# Battery_old.net
KiCad netlist of a schematic drawn in Altium Designer
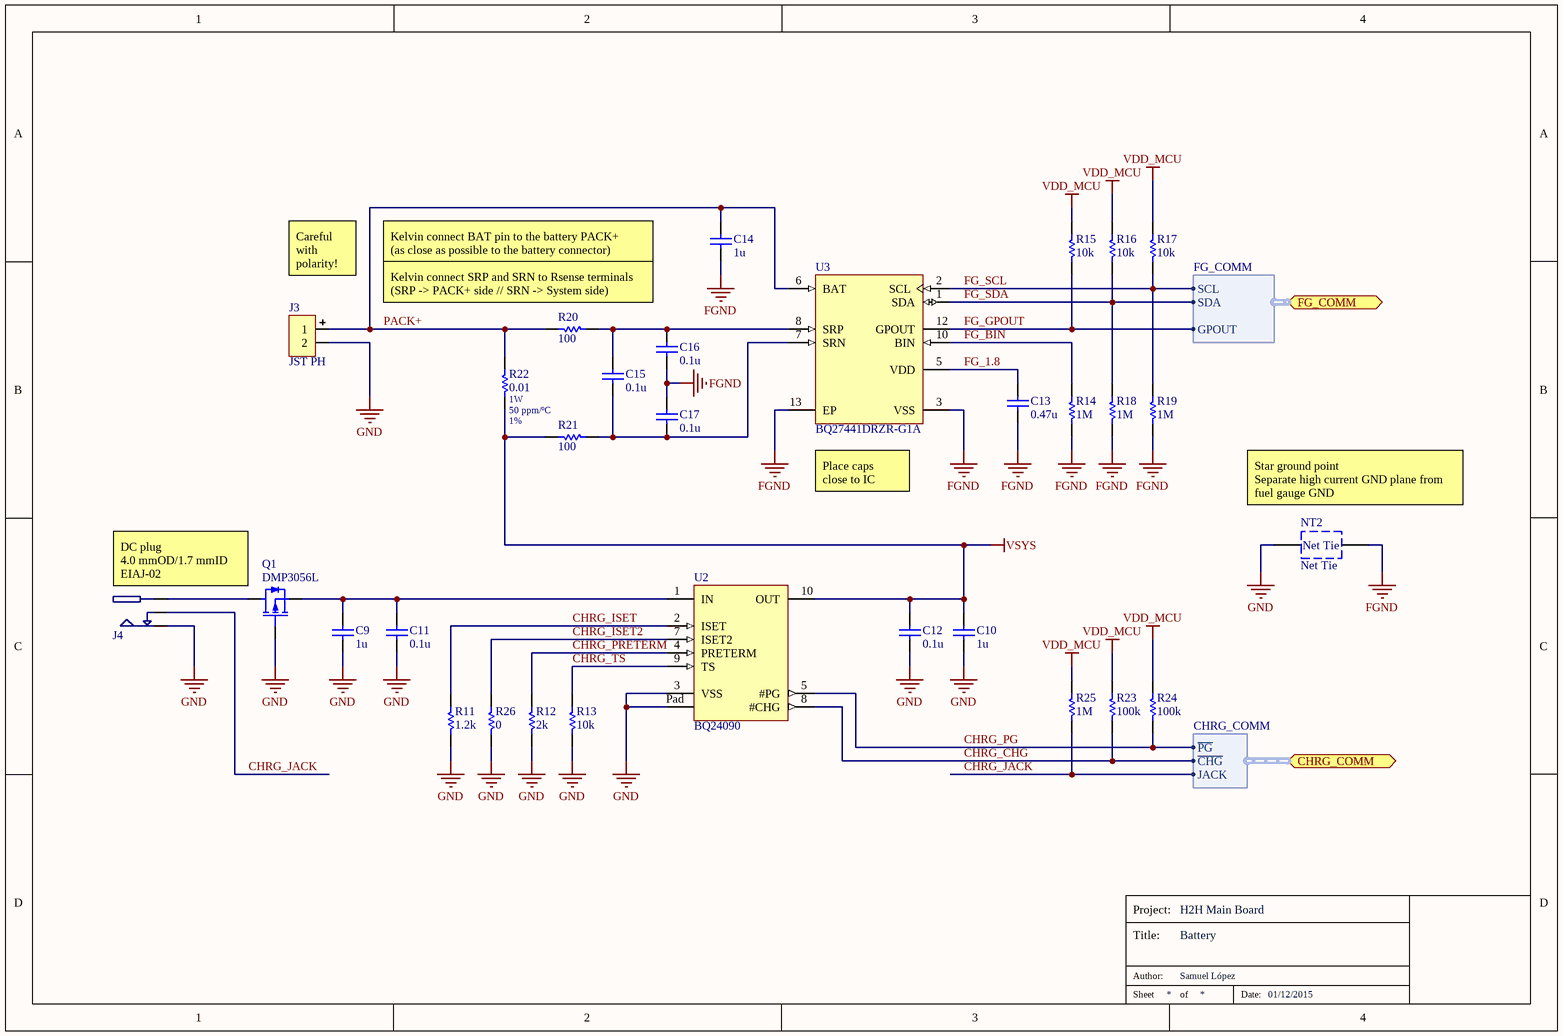
[diagram p0: Battery_old.SchDoc]

(export (version "E")
  (design (tool "Eeschema 10.0.6"))
  (components
    (comp (ref "C9")
      (value "1u")
      (footprint "C0603")
      (description "Capacitor")
      (libsource (lib "Common Devices") (part "Capacitor"))
    )
    (comp (ref "C10")
      (value "1u")
      (footprint "C0603")
      (description "Capacitor")
      (libsource (lib "Common Devices") (part "Capacitor"))
    )
    (comp (ref "C11")
      (value "0.1u")
      (footprint "C0603")
      (description "Capacitor")
      (libsource (lib "Common Devices") (part "Capacitor"))
    )
    (comp (ref "C12")
      (value "0.1u")
      (footprint "C0603")
      (description "Capacitor")
      (libsource (lib "Common Devices") (part "Capacitor"))
    )
    (comp (ref "C13")
      (value "0.47u")
      (footprint "C0603")
      (description "Capacitor")
      (libsource (lib "Common Devices") (part "Capacitor"))
    )
    (comp (ref "C14")
      (value "1u")
      (footprint "C0603")
      (description "Capacitor")
      (libsource (lib "Common Devices") (part "Capacitor"))
    )
    (comp (ref "C15")
      (value "0.1u")
      (footprint "C0603")
      (description "Capacitor")
      (libsource (lib "Common Devices") (part "Capacitor"))
    )
    (comp (ref "C16")
      (value "0.1u")
      (footprint "C0603")
      (description "Capacitor")
      (libsource (lib "Common Devices") (part "Capacitor"))
    )
    (comp (ref "C17")
      (value "0.1u")
      (footprint "C0603")
      (description "Capacitor")
      (libsource (lib "Common Devices") (part "Capacitor"))
    )
    (comp (ref "J3")
      (value "JST PH")
      (footprint "JST PH 2 Socket")
      (description "JST PH 2 Pin Socket")
      (libsource (lib "Common Devices") (part "JST PH 2 Pin Socket"))
    )
    (comp (ref "J4")
      (value "DC Plug")
      (footprint "PJ-018H-SMT")
      (description "DC Power Plug - 4.0 mmOD / 1.7 mmID")
      (libsource (lib "Common Devices") (part "PJ-018H-SMT"))
    )
    (comp (ref "NT2")
      (value "Net Tie")
      (footprint "Net Tie (AGND-DGND)")
      (description "Net Tie (AGND-DGND)")
      (libsource (lib "Common Devices") (part "Net Tie"))
    )
    (comp (ref "Q1")
      (value "DMP3056L")
      (footprint "SSOT-3")
      (description "Transistor, MOSFET, P-Channel, 30V, 4.3A")
      (libsource (lib "Common Devices") (part "DMP3056L"))
    )
    (comp (ref "R11")
      (value "1.2k")
      (footprint "R0603")
      (description "Resistor")
      (libsource (lib "Common Devices") (part "Resistor"))
    )
    (comp (ref "R12")
      (value "2k")
      (footprint "R0603")
      (description "Resistor")
      (libsource (lib "Common Devices") (part "Resistor"))
    )
    (comp (ref "R13")
      (value "10k")
      (footprint "R0603")
      (description "Resistor")
      (libsource (lib "Common Devices") (part "Resistor"))
    )
    (comp (ref "R14")
      (value "1M")
      (footprint "R0603")
      (description "Resistor")
      (libsource (lib "Common Devices") (part "Resistor"))
    )
    (comp (ref "R15")
      (value "10k")
      (footprint "R0603")
      (description "Resistor")
      (libsource (lib "Common Devices") (part "Resistor"))
    )
    (comp (ref "R16")
      (value "10k")
      (footprint "R0603")
      (description "Resistor")
      (libsource (lib "Common Devices") (part "Resistor"))
    )
    (comp (ref "R17")
      (value "10k")
      (footprint "R0603")
      (description "Resistor")
      (libsource (lib "Common Devices") (part "Resistor"))
    )
    (comp (ref "R18")
      (value "1M")
      (footprint "R0603")
      (description "Resistor")
      (libsource (lib "Common Devices") (part "Resistor"))
    )
    (comp (ref "R19")
      (value "1M")
      (footprint "R0603")
      (description "Resistor")
      (libsource (lib "Common Devices") (part "Resistor"))
    )
    (comp (ref "R20")
      (value "100")
      (footprint "R0603")
      (description "Resistor")
      (libsource (lib "Common Devices") (part "Resistor"))
    )
    (comp (ref "R21")
      (value "100")
      (footprint "R0603")
      (description "Resistor")
      (libsource (lib "Common Devices") (part "Resistor"))
    )
    (comp (ref "R22")
      (value "0.01")
      (footprint "R1206")
      (description "Resistor")
      (fields (field (name "POWER") "1W") (field (name "TCR") "50 ppm/ºC") (field (name "TOLERANCE") "1%"))
      (libsource (lib "Common Devices") (part "Resistor"))
    )
    (comp (ref "R23")
      (value "100k")
      (footprint "R0603")
      (description "Resistor")
      (libsource (lib "Common Devices") (part "Resistor"))
    )
    (comp (ref "R24")
      (value "100k")
      (footprint "R0603")
      (description "Resistor")
      (libsource (lib "Common Devices") (part "Resistor"))
    )
    (comp (ref "R25")
      (value "1M")
      (footprint "R0603")
      (description "Resistor")
      (libsource (lib "Common Devices") (part "Resistor"))
    )
    (comp (ref "R26")
      (value "0")
      (footprint "R0603")
      (description "Resistor")
      (libsource (lib "Common Devices") (part "Resistor"))
    )
    (comp (ref "U2")
      (value "BQ24090")
      (footprint "TSSOP50P490X110_HS-11N")
      (description "Battery Charger, Single Cell Li-Ion/LiPo, 1A")
      (libsource (lib "Main Board") (part "BQ24090"))
    )
    (comp (ref "U3")
      (value "BQ27441DRZR-G1A")
      (footprint "DRZ12-1950X2450TP")
      (description "System-Side Impedance Track Fuel Gauge, -40 to 85 degC, 12-pin SON (DRZ), Green (RoHS & no Sb/Br)")
      (fields (field (name "PARTNUMBER") "BQ27410DRZR-G1") (field (name "MANUFACTURER") "Texas Instruments"))
      (libsource (lib "Main Board") (part "BQ27441DRZR-G1A"))
    )
  )
  (nets
    (net (code "3") (name "/CHRG_CHG") (class "Default")
      (node (ref "R23") (pin "1") (pinfunction "1_1") (pintype "passive"))
      (node (ref "U2") (pin "8") (pinfunction "#CHG_8") (pintype "output"))
    )
    (net (code "4") (name "/CHRG_ISET") (class "Default")
      (node (ref "R11") (pin "2") (pinfunction "2_2") (pintype "passive"))
      (node (ref "U2") (pin "2") (pinfunction "ISET_2") (pintype "input"))
    )
    (net (code "5") (name "/CHRG_ISET2") (class "Default")
      (node (ref "R26") (pin "2") (pinfunction "2_2") (pintype "passive"))
      (node (ref "U2") (pin "7") (pinfunction "ISET2_7") (pintype "input"))
    )
    (net (code "6") (name "/CHRG_JACK") (class "Default")
      (node (ref "J4") (pin "3") (pinfunction "3_3") (pintype "passive"))
      (node (ref "R25") (pin "1") (pinfunction "1_1") (pintype "passive"))
    )
    (net (code "7") (name "/CHRG_PG") (class "Default")
      (node (ref "R24") (pin "1") (pinfunction "1_1") (pintype "passive"))
      (node (ref "U2") (pin "5") (pinfunction "#PG_5") (pintype "output"))
    )
    (net (code "8") (name "/CHRG_PRETERM") (class "Default")
      (node (ref "R12") (pin "2") (pinfunction "2_2") (pintype "passive"))
      (node (ref "U2") (pin "4") (pinfunction "PRETERM_4") (pintype "input"))
    )
    (net (code "9") (name "/CHRG_TS") (class "Default")
      (node (ref "R13") (pin "2") (pinfunction "2_2") (pintype "passive"))
      (node (ref "U2") (pin "9") (pinfunction "TS_9") (pintype "input"))
    )
    (net (code "10") (name "/FG_1.8") (class "Default")
      (node (ref "C13") (pin "2") (pinfunction "2_2") (pintype "passive"))
      (node (ref "U3") (pin "5") (pinfunction "VDD_5") (pintype "power_in"))
    )
    (net (code "11") (name "/FG_BIN") (class "Default")
      (node (ref "R14") (pin "2") (pinfunction "2_2") (pintype "passive"))
      (node (ref "U3") (pin "10") (pinfunction "BIN_10") (pintype "input"))
    )
    (net (code "12") (name "/FG_GPOUT") (class "Default")
      (node (ref "R15") (pin "1") (pinfunction "1_1") (pintype "passive"))
      (node (ref "U3") (pin "12") (pinfunction "GPOUT_12") (pintype "open_collector"))
    )
    (net (code "13") (name "/FG_SCL") (class "Default")
      (node (ref "R17") (pin "1") (pinfunction "1_1") (pintype "passive"))
      (node (ref "R19") (pin "2") (pinfunction "2_2") (pintype "passive"))
      (node (ref "U3") (pin "2") (pinfunction "SCL_2") (pintype "input"))
    )
    (net (code "14") (name "/FG_SDA") (class "Default")
      (node (ref "R16") (pin "1") (pinfunction "1_1") (pintype "passive"))
      (node (ref "R18") (pin "2") (pinfunction "2_2") (pintype "passive"))
      (node (ref "U3") (pin "1") (pinfunction "SDA_1") (pintype "bidirectional"))
    )
    (net (code "15") (name "/PACK+") (class "Default")
      (node (ref "C14") (pin "2") (pinfunction "2_2") (pintype "passive"))
      (node (ref "J3") (pin "1") (pinfunction "1_1") (pintype "passive"))
      (node (ref "R20") (pin "1") (pinfunction "1_1") (pintype "passive"))
      (node (ref "R22") (pin "1") (pinfunction "1_1") (pintype "passive"))
      (node (ref "U3") (pin "6") (pinfunction "BAT_6") (pintype "input"))
    )
    (net (code "18") (name "FGND") (class "Default")
      (node (ref "C13") (pin "1") (pinfunction "1_1") (pintype "passive"))
      (node (ref "C14") (pin "1") (pinfunction "1_1") (pintype "passive"))
      (node (ref "C16") (pin "1") (pinfunction "1_1") (pintype "passive"))
      (node (ref "C17") (pin "2") (pinfunction "2_2") (pintype "passive"))
      (node (ref "NT2") (pin "2") (pinfunction "2_2") (pintype "passive"))
      (node (ref "R14") (pin "1") (pinfunction "1_1") (pintype "passive"))
      (node (ref "R18") (pin "1") (pinfunction "1_1") (pintype "passive"))
      (node (ref "R19") (pin "1") (pinfunction "1_1") (pintype "passive"))
      (node (ref "U3") (pin "13") (pinfunction "EP_13") (pintype "passive"))
      (node (ref "U3") (pin "3") (pinfunction "VSS_3") (pintype "power_in"))
    )
    (net (code "19") (name "GND") (class "Default")
      (node (ref "C10") (pin "1") (pinfunction "1_1") (pintype "passive"))
      (node (ref "C11") (pin "1") (pinfunction "1_1") (pintype "passive"))
      (node (ref "C12") (pin "1") (pinfunction "1_1") (pintype "passive"))
      (node (ref "C9") (pin "1") (pinfunction "1_1") (pintype "passive"))
      (node (ref "J3") (pin "2") (pinfunction "2_2") (pintype "passive"))
      (node (ref "J4") (pin "2") (pinfunction "2_2") (pintype "passive"))
      (node (ref "NT2") (pin "1") (pinfunction "1_1") (pintype "passive"))
      (node (ref "Q1") (pin "1") (pinfunction "G_1") (pintype "passive"))
      (node (ref "R11") (pin "1") (pinfunction "1_1") (pintype "passive"))
      (node (ref "R12") (pin "1") (pinfunction "1_1") (pintype "passive"))
      (node (ref "R13") (pin "1") (pinfunction "1_1") (pintype "passive"))
      (node (ref "R26") (pin "1") (pinfunction "1_1") (pintype "passive"))
      (node (ref "U2") (pin "3") (pinfunction "VSS_3") (pintype "power_in"))
      (node (ref "U2") (pin "Pad") (pinfunction "Thermal_Pad") (pintype "passive"))
    )
    (net (code "20") (name "Net-(Q1-D)") (class "Default")
      (node (ref "J4") (pin "1") (pinfunction "1_1") (pintype "passive"))
      (node (ref "Q1") (pin "3") (pinfunction "D_3") (pintype "passive"))
    )
    (net (code "21") (name "Net-(Q1-S)") (class "Default")
      (node (ref "C11") (pin "2") (pinfunction "2_2") (pintype "passive"))
      (node (ref "C9") (pin "2") (pinfunction "2_2") (pintype "passive"))
      (node (ref "Q1") (pin "2") (pinfunction "S_2") (pintype "passive"))
      (node (ref "U2") (pin "1") (pinfunction "IN_1") (pintype "power_in"))
    )
    (net (code "22") (name "Net-(U3-SRN)") (class "Default")
      (node (ref "C15") (pin "1") (pinfunction "1_1") (pintype "passive"))
      (node (ref "C17") (pin "1") (pinfunction "1_1") (pintype "passive"))
      (node (ref "R21") (pin "2") (pinfunction "2_2") (pintype "passive"))
      (node (ref "U3") (pin "7") (pinfunction "SRN_7") (pintype "input"))
    )
    (net (code "23") (name "Net-(U3-SRP)") (class "Default")
      (node (ref "C15") (pin "2") (pinfunction "2_2") (pintype "passive"))
      (node (ref "C16") (pin "2") (pinfunction "2_2") (pintype "passive"))
      (node (ref "R20") (pin "2") (pinfunction "2_2") (pintype "passive"))
      (node (ref "U3") (pin "8") (pinfunction "SRP_8") (pintype "input"))
    )
    (net (code "24") (name "VDD_MCU") (class "Default")
      (node (ref "R15") (pin "2") (pinfunction "2_2") (pintype "passive"))
      (node (ref "R16") (pin "2") (pinfunction "2_2") (pintype "passive"))
      (node (ref "R17") (pin "2") (pinfunction "2_2") (pintype "passive"))
      (node (ref "R23") (pin "2") (pinfunction "2_2") (pintype "passive"))
      (node (ref "R24") (pin "2") (pinfunction "2_2") (pintype "passive"))
      (node (ref "R25") (pin "2") (pinfunction "2_2") (pintype "passive"))
    )
    (net (code "25") (name "VSYS") (class "Default")
      (node (ref "C10") (pin "2") (pinfunction "2_2") (pintype "passive"))
      (node (ref "C12") (pin "2") (pinfunction "2_2") (pintype "passive"))
      (node (ref "R21") (pin "1") (pinfunction "1_1") (pintype "passive"))
      (node (ref "R22") (pin "2") (pinfunction "2_2") (pintype "passive"))
      (node (ref "U2") (pin "10") (pinfunction "OUT_10") (pintype "power_in"))
    )
  )
)
